# Arduino_extension_connectors.net
KiCad netlist of a schematic drawn in Altium Designer
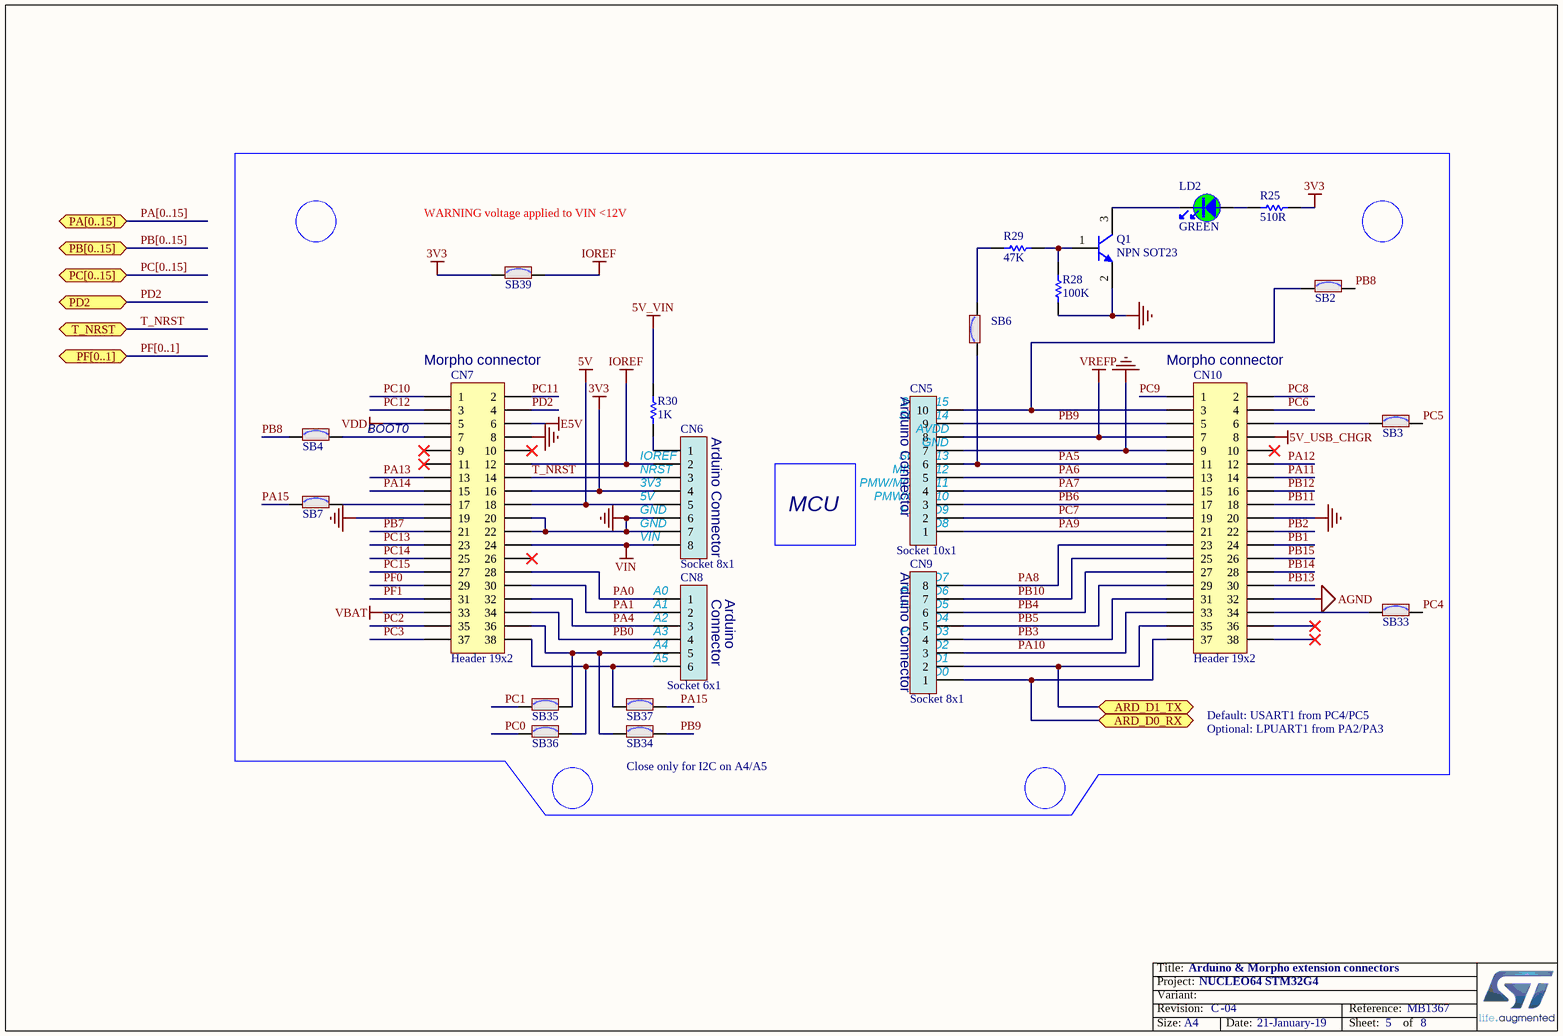
[diagram p0: Arduino_extension_connectors.SchDoc]

(export (version "E")
  (design (tool "Eeschema 10.0.6"))
  (components
    (comp (ref "CN5")
      (value "Socket 10x1")
      (footprint "CON_SAMTEC_SSW-110-03-X-S")
      (description "Socket, 10x1, 2.54mm, VR, TH, Height 8.51mm/10mm")
      (fields
        (field (name "INTERNAL_PART_NUMBER") "MCD-00262")
        (field (name "MANUFACTURER_PART_NUMBER") "SSW-110-03-x-S")
        (field (name "PROVIDED_BY") "SUBCO")
      )
      (libsource (lib "MCD_PARTS_database") (part "Socket 10x1"))
    )
    (comp (ref "CN6")
      (value "Socket 8x1")
      (footprint "CON_SAMTEC_SSW-108-03-X-S")
      (description "Socket, 8x1, 2.54mm, VR, TH, Height 8.51mm/10mm")
      (fields
        (field (name "INTERNAL_PART_NUMBER") "MCD-00261")
        (field (name "MANUFACTURER_PART_NUMBER") "SSW-108-03-x-S")
        (field (name "PROVIDED_BY") "SUBCO")
      )
      (libsource (lib "MCD_PARTS_database") (part "Socket 8x1"))
    )
    (comp (ref "CN7")
      (value "Header 19x2")
      (footprint "CON_SAMTEC_TSW-119-09-X-D")
      (description "Header, 19x2, 2,54mm, VR, TH, Height 5.84mm/10.16mm")
      (fields
        (field (name "INTERNAL_PART_NUMBER") "MCD-00213")
        (field (name "MANUFACTURER_PART_NUMBER") "TSW-119-09-x-D")
        (field (name "PROVIDED_BY") "SUBCO")
      )
      (libsource (lib "MCD_PARTS_database") (part "Header 19x2"))
    )
    (comp (ref "CN8")
      (value "Socket 6x1")
      (footprint "CON_SAMTEC_SSW-106-03-X-S")
      (description "Socket, 6x1, 2.54mm, VR, TH, Height 8.51mm/10mm")
      (fields
        (field (name "INTERNAL_PART_NUMBER") "MCD-00260")
        (field (name "MANUFACTURER_PART_NUMBER") "SSW-106-03-x-S")
        (field (name "PROVIDED_BY") "SUBCO")
      )
      (libsource (lib "MCD_PARTS_database") (part "Socket 6x1"))
    )
    (comp (ref "CN9")
      (value "Socket 8x1")
      (footprint "CON_SAMTEC_SSW-108-03-X-S")
      (description "Socket, 8x1, 2.54mm, VR, TH, Height 8.51mm/10mm")
      (fields
        (field (name "INTERNAL_PART_NUMBER") "MCD-00261")
        (field (name "MANUFACTURER_PART_NUMBER") "SSW-108-03-x-S")
        (field (name "PROVIDED_BY") "SUBCO")
      )
      (libsource (lib "") (part "Socket 8x1_1"))
    )
    (comp (ref "CN10")
      (value "Header 19x2")
      (footprint "CON_SAMTEC_TSW-119-09-X-D")
      (description "Header, 19x2, 2,54mm, VR, TH, Height 5.84mm/10.16mm")
      (fields
        (field (name "INTERNAL_PART_NUMBER") "MCD-00213")
        (field (name "MANUFACTURER_PART_NUMBER") "TSW-119-09-x-D")
        (field (name "PROVIDED_BY") "SUBCO")
      )
      (libsource (lib "MCD_PARTS_database") (part "Header 19x2"))
    )
    (comp (ref "LD2")
      (value "GREEN")
      (footprint "LED_0603_GREEN")
      (description "LED, Green, 0603")
      (fields
        (field (name "INTERNAL_PART_NUMBER") "MCD-00050")
        (field (name "MANUFACTURER_PART_NUMBER") "19-213SYGC/S530-E2/TR8")
        (field (name "PROVIDED_BY") "SUBCO")
      )
      (libsource (lib "MCD_PARTS_database") (part "LED_green"))
    )
    (comp (ref "Q1")
      (value "NPN SOT23")
      (footprint "NPN_SOT23")
      (description "NPN Bipolar Transistor")
      (fields
        (field (name "INTERNAL_PART_NUMBER") "MCD-00073")
        (field (name "MANUFACTURER_PART_NUMBER") "BSR14")
        (field (name "PROVIDED_BY") "SUBCO")
      )
      (libsource (lib "MCD_PARTS_database") (part "9013-SOT23"))
    )
    (comp (ref "R25")
      (value "510R")
      (footprint "R0603")
      (description "Resistor,510R,0603,1%,1/10W")
      (fields
        (field (name "INTERNAL_PART_NUMBER") "MCD-00225")
        (field (name "MANUFACTURER_PART_NUMBER") "RC0603FR-07510RL")
        (field (name "PROVIDED_BY") "SUBCO")
      )
      (libsource (lib "MCD_PARTS_database") (part "Resistor"))
    )
    (comp (ref "R28")
      (value "100K")
      (footprint "R0603")
      (description "Resistor,100K,0603,1%,1/10W")
      (fields
        (field (name "INTERNAL_PART_NUMBER") "MCD-00223")
        (field (name "MANUFACTURER_PART_NUMBER") "RC0603FR-07100KL")
        (field (name "PROVIDED_BY") "Subcon")
      )
      (libsource (lib "MCD_PARTS_database") (part "Resistor"))
    )
    (comp (ref "R29")
      (value "47K")
      (footprint "R0603")
      (description "Resistor,47K,0603,1%,1/10W")
      (fields
        (field (name "INTERNAL_PART_NUMBER") "MCD-00222")
        (field (name "MANUFACTURER_PART_NUMBER") "RC0603FR-0747KL")
        (field (name "PROVIDED_BY") "SUBCO")
      )
      (libsource (lib "MCD_PARTS_database") (part "Resistor"))
    )
    (comp (ref "R30")
      (value "1K")
      (footprint "R0603")
      (description "Resistor,1K,0603,1%,1/10W")
      (fields
        (field (name "INTERNAL_PART_NUMBER") "MCD-00070")
        (field (name "MANUFACTURER_PART_NUMBER") "RC0603FR-071KL")
        (field (name "PROVIDED_BY") "Subcon")
      )
      (libsource (lib "MCD_PARTS_database") (part "Resistor"))
    )
    (comp (ref "SB2")
      (value "~")
      (footprint "SOLDER-BRIDGE_R0603-0R")
      (description "Solder Bridge ON")
      (fields
        (field (name "INTERNAL_PART_NUMBER") "MCD-00071")
        (field (name "MANUFACTURER_PART_NUMBER") "RC0603JR-070RL")
        (field (name "PROVIDED_BY") "SUBCO")
      )
      (libsource (lib "MCD_PARTS_database") (part "SB_ON"))
    )
    (comp (ref "SB3")
      (value "~")
      (footprint "SOLDER-BRIDGE_R0603-0R")
      (description "Solder Bridge ON")
      (fields
        (field (name "INTERNAL_PART_NUMBER") "MCD-00071")
        (field (name "MANUFACTURER_PART_NUMBER") "RC0603JR-070RL")
        (field (name "PROVIDED_BY") "SUBCO")
      )
      (libsource (lib "MCD_PARTS_database") (part "SB_ON"))
    )
    (comp (ref "SB4")
      (value "~")
      (footprint "SOLDER-BRIDGE_R0603-0R")
      (description "Solder Bridge ON")
      (fields
        (field (name "INTERNAL_PART_NUMBER") "MCD-00071")
        (field (name "MANUFACTURER_PART_NUMBER") "RC0603JR-070RL")
        (field (name "PROVIDED_BY") "SUBCO")
      )
      (libsource (lib "MCD_PARTS_database") (part "SB_ON"))
    )
    (comp (ref "SB6")
      (value "~")
      (footprint "SOLDER-BRIDGE_R0603-0R")
      (description "Solder Bridge ON")
      (fields
        (field (name "INTERNAL_PART_NUMBER") "MCD-00071")
        (field (name "MANUFACTURER_PART_NUMBER") "RC0603JR-070RL")
        (field (name "PROVIDED_BY") "SUBCO")
      )
      (libsource (lib "") (part "SB_ON_1"))
    )
    (comp (ref "SB7")
      (value "~")
      (footprint "SOLDER-BRIDGE_R0603-0R")
      (description "Solder Bridge ON")
      (fields
        (field (name "INTERNAL_PART_NUMBER") "MCD-00071")
        (field (name "MANUFACTURER_PART_NUMBER") "RC0603JR-070RL")
        (field (name "PROVIDED_BY") "SUBCO")
      )
      (libsource (lib "MCD_PARTS_database") (part "SB_ON"))
    )
    (comp (ref "SB33")
      (value "~")
      (footprint "SOLDER-BRIDGE_R0603-0R")
      (description "Solder Bridge ON")
      (fields
        (field (name "INTERNAL_PART_NUMBER") "MCD-00071")
        (field (name "MANUFACTURER_PART_NUMBER") "RC0603JR-070RL")
        (field (name "PROVIDED_BY") "SUBCO")
      )
      (libsource (lib "MCD_PARTS_database") (part "SB_ON"))
    )
    (comp (ref "SB34")
      (value "~")
      (footprint "SOLDER-BRIDGE_R0603-0R")
      (description "Solder Bridge ON")
      (fields
        (field (name "INTERNAL_PART_NUMBER") "MCD-00071")
        (field (name "MANUFACTURER_PART_NUMBER") "RC0603JR-070RL")
        (field (name "PROVIDED_BY") "SUBCO")
      )
      (libsource (lib "MCD_PARTS_database") (part "SB_ON"))
    )
    (comp (ref "SB35")
      (value "~")
      (footprint "SOLDER-BRIDGE_R0603-0R")
      (description "Solder Bridge ON")
      (fields
        (field (name "INTERNAL_PART_NUMBER") "MCD-00071")
        (field (name "MANUFACTURER_PART_NUMBER") "RC0603JR-070RL")
        (field (name "PROVIDED_BY") "SUBCO")
      )
      (libsource (lib "MCD_PARTS_database") (part "SB_ON"))
    )
    (comp (ref "SB36")
      (value "~")
      (footprint "SOLDER-BRIDGE_R0603-0R")
      (description "Solder Bridge ON")
      (fields
        (field (name "INTERNAL_PART_NUMBER") "MCD-00071")
        (field (name "MANUFACTURER_PART_NUMBER") "RC0603JR-070RL")
        (field (name "PROVIDED_BY") "SUBCO")
      )
      (libsource (lib "MCD_PARTS_database") (part "SB_ON"))
    )
    (comp (ref "SB37")
      (value "~")
      (footprint "SOLDER-BRIDGE_R0603-0R")
      (description "Solder Bridge ON")
      (fields
        (field (name "INTERNAL_PART_NUMBER") "MCD-00071")
        (field (name "MANUFACTURER_PART_NUMBER") "RC0603JR-070RL")
        (field (name "PROVIDED_BY") "SUBCO")
      )
      (libsource (lib "MCD_PARTS_database") (part "SB_ON"))
    )
    (comp (ref "SB39")
      (value "~")
      (footprint "SOLDER-BRIDGE_R0603-0R")
      (description "Solder Bridge ON")
      (fields
        (field (name "INTERNAL_PART_NUMBER") "MCD-00071")
        (field (name "MANUFACTURER_PART_NUMBER") "RC0603JR-070RL")
        (field (name "PROVIDED_BY") "SUBCO")
      )
      (libsource (lib "MCD_PARTS_database") (part "SB_ON"))
    )
  )
  (nets
    (net (code "3") (name "/ARD_D0_RX") (class "Default")
      (node (ref "CN10") (pin "37") (pinfunction "37_37") (pintype "passive"))
      (node (ref "CN9") (pin "1") (pinfunction "1_1") (pintype "passive"))
    )
    (net (code "4") (name "/ARD_D1_TX") (class "Default")
      (node (ref "CN10") (pin "35") (pinfunction "35_35") (pintype "passive"))
      (node (ref "CN9") (pin "2") (pinfunction "2_2") (pintype "passive"))
    )
    (net (code "5") (name "/PA0") (class "Default")
      (node (ref "CN7") (pin "28") (pinfunction "28_28") (pintype "passive"))
      (node (ref "CN8") (pin "1") (pinfunction "1_1") (pintype "passive"))
    )
    (net (code "6") (name "/PA1") (class "Default")
      (node (ref "CN7") (pin "30") (pinfunction "30_30") (pintype "passive"))
      (node (ref "CN8") (pin "2") (pinfunction "2_2") (pintype "passive"))
    )
    (net (code "7") (name "/PA4") (class "Default")
      (node (ref "CN7") (pin "32") (pinfunction "32_32") (pintype "passive"))
      (node (ref "CN8") (pin "3") (pinfunction "3_3") (pintype "passive"))
    )
    (net (code "8") (name "/PA5") (class "Default")
      (node (ref "CN10") (pin "11") (pinfunction "11_11") (pintype "passive"))
      (node (ref "CN5") (pin "6") (pinfunction "6_6") (pintype "passive"))
      (node (ref "SB6") (pin "1") (pinfunction "1_1") (pintype "passive"))
    )
    (net (code "9") (name "/PA6") (class "Default")
      (node (ref "CN10") (pin "13") (pinfunction "13_13") (pintype "passive"))
      (node (ref "CN5") (pin "5") (pinfunction "5_5") (pintype "passive"))
    )
    (net (code "10") (name "/PA7") (class "Default")
      (node (ref "CN10") (pin "15") (pinfunction "15_15") (pintype "passive"))
      (node (ref "CN5") (pin "4") (pinfunction "4_4") (pintype "passive"))
    )
    (net (code "11") (name "/PA8") (class "Default")
      (node (ref "CN10") (pin "23") (pinfunction "23_23") (pintype "passive"))
      (node (ref "CN9") (pin "8") (pinfunction "8_8") (pintype "passive"))
    )
    (net (code "12") (name "/PA9") (class "Default")
      (node (ref "CN10") (pin "21") (pinfunction "21_21") (pintype "passive"))
      (node (ref "CN5") (pin "1") (pinfunction "1_1") (pintype "passive"))
    )
    (net (code "13") (name "/PA10") (class "Default")
      (node (ref "CN10") (pin "33") (pinfunction "33_33") (pintype "passive"))
      (node (ref "CN9") (pin "3") (pinfunction "3_3") (pintype "passive"))
    )
    (net (code "14") (name "/PA11") (class "Default")
      (node (ref "CN10") (pin "14") (pinfunction "14_14") (pintype "passive"))
    )
    (net (code "15") (name "/PA12") (class "Default")
      (node (ref "CN10") (pin "12") (pinfunction "12_12") (pintype "passive"))
    )
    (net (code "16") (name "/PA13") (class "Default")
      (node (ref "CN7") (pin "13") (pinfunction "13_13") (pintype "passive"))
    )
    (net (code "17") (name "/PA14") (class "Default")
      (node (ref "CN7") (pin "15") (pinfunction "15_15") (pintype "passive"))
    )
    (net (code "18") (name "/PA15") (class "Default")
      (node (ref "SB37") (pin "2") (pinfunction "2_2") (pintype "passive"))
      (node (ref "SB7") (pin "1") (pinfunction "1_1") (pintype "passive"))
    )
    (net (code "20") (name "/PB0") (class "Default")
      (node (ref "CN7") (pin "34") (pinfunction "34_34") (pintype "passive"))
      (node (ref "CN8") (pin "4") (pinfunction "4_4") (pintype "passive"))
    )
    (net (code "21") (name "/PB1") (class "Default")
      (node (ref "CN10") (pin "24") (pinfunction "24_24") (pintype "passive"))
    )
    (net (code "22") (name "/PB2") (class "Default")
      (node (ref "CN10") (pin "22") (pinfunction "22_22") (pintype "passive"))
    )
    (net (code "23") (name "/PB3") (class "Default")
      (node (ref "CN10") (pin "31") (pinfunction "31_31") (pintype "passive"))
      (node (ref "CN9") (pin "4") (pinfunction "4_4") (pintype "passive"))
    )
    (net (code "24") (name "/PB4") (class "Default")
      (node (ref "CN10") (pin "27") (pinfunction "27_27") (pintype "passive"))
      (node (ref "CN9") (pin "6") (pinfunction "6_6") (pintype "passive"))
    )
    (net (code "25") (name "/PB5") (class "Default")
      (node (ref "CN10") (pin "29") (pinfunction "29_29") (pintype "passive"))
      (node (ref "CN9") (pin "5") (pinfunction "5_5") (pintype "passive"))
    )
    (net (code "26") (name "/PB6") (class "Default")
      (node (ref "CN10") (pin "17") (pinfunction "17_17") (pintype "passive"))
      (node (ref "CN5") (pin "3") (pinfunction "3_3") (pintype "passive"))
    )
    (net (code "27") (name "/PB7") (class "Default")
      (node (ref "CN7") (pin "21") (pinfunction "21_21") (pintype "passive"))
    )
    (net (code "28") (name "/PB8") (class "Default")
      (node (ref "SB2") (pin "2") (pinfunction "2_2") (pintype "passive"))
      (node (ref "SB4") (pin "1") (pinfunction "1_1") (pintype "passive"))
    )
    (net (code "29") (name "/PB9") (class "Default")
      (node (ref "CN10") (pin "5") (pinfunction "5_5") (pintype "passive"))
      (node (ref "CN5") (pin "9") (pinfunction "9_9") (pintype "passive"))
      (node (ref "SB34") (pin "2") (pinfunction "2_2") (pintype "passive"))
    )
    (net (code "30") (name "/PB10") (class "Default")
      (node (ref "CN10") (pin "25") (pinfunction "25_25") (pintype "passive"))
      (node (ref "CN9") (pin "7") (pinfunction "7_7") (pintype "passive"))
    )
    (net (code "31") (name "/PB11") (class "Default")
      (node (ref "CN10") (pin "18") (pinfunction "18_18") (pintype "passive"))
    )
    (net (code "32") (name "/PB12") (class "Default")
      (node (ref "CN10") (pin "16") (pinfunction "16_16") (pintype "passive"))
    )
    (net (code "33") (name "/PB13") (class "Default")
      (node (ref "CN10") (pin "30") (pinfunction "30_30") (pintype "passive"))
    )
    (net (code "34") (name "/PB14") (class "Default")
      (node (ref "CN10") (pin "28") (pinfunction "28_28") (pintype "passive"))
    )
    (net (code "35") (name "/PB15") (class "Default")
      (node (ref "CN10") (pin "26") (pinfunction "26_26") (pintype "passive"))
    )
    (net (code "37") (name "/PC0") (class "Default")
      (node (ref "SB36") (pin "1") (pinfunction "1_1") (pintype "passive"))
    )
    (net (code "38") (name "/PC1") (class "Default")
      (node (ref "SB35") (pin "1") (pinfunction "1_1") (pintype "passive"))
    )
    (net (code "39") (name "/PC2") (class "Default")
      (node (ref "CN7") (pin "35") (pinfunction "35_35") (pintype "passive"))
    )
    (net (code "40") (name "/PC3") (class "Default")
      (node (ref "CN7") (pin "37") (pinfunction "37_37") (pintype "passive"))
    )
    (net (code "41") (name "/PC4") (class "Default")
      (node (ref "SB33") (pin "2") (pinfunction "2_2") (pintype "passive"))
    )
    (net (code "42") (name "/PC5") (class "Default")
      (node (ref "SB3") (pin "2") (pinfunction "2_2") (pintype "passive"))
    )
    (net (code "43") (name "/PC6") (class "Default")
      (node (ref "CN10") (pin "4") (pinfunction "4_4") (pintype "passive"))
    )
    (net (code "44") (name "/PC7") (class "Default")
      (node (ref "CN10") (pin "19") (pinfunction "19_19") (pintype "passive"))
      (node (ref "CN5") (pin "2") (pinfunction "2_2") (pintype "passive"))
    )
    (net (code "45") (name "/PC8") (class "Default")
      (node (ref "CN10") (pin "2") (pinfunction "2_2") (pintype "passive"))
    )
    (net (code "46") (name "/PC9") (class "Default")
      (node (ref "CN10") (pin "1") (pinfunction "1_1") (pintype "passive"))
    )
    (net (code "47") (name "/PC10") (class "Default")
      (node (ref "CN7") (pin "1") (pinfunction "1_1") (pintype "passive"))
    )
    (net (code "48") (name "/PC11") (class "Default")
      (node (ref "CN7") (pin "2") (pinfunction "2_2") (pintype "passive"))
    )
    (net (code "49") (name "/PC12") (class "Default")
      (node (ref "CN7") (pin "3") (pinfunction "3_3") (pintype "passive"))
    )
    (net (code "50") (name "/PC13") (class "Default")
      (node (ref "CN7") (pin "23") (pinfunction "23_23") (pintype "passive"))
    )
    (net (code "51") (name "/PC14") (class "Default")
      (node (ref "CN7") (pin "25") (pinfunction "25_25") (pintype "passive"))
    )
    (net (code "52") (name "/PC15") (class "Default")
      (node (ref "CN7") (pin "27") (pinfunction "27_27") (pintype "passive"))
    )
    (net (code "54") (name "/PD2") (class "Default")
      (node (ref "CN7") (pin "4") (pinfunction "4_4") (pintype "passive"))
    )
    (net (code "55") (name "/PF0") (class "Default")
      (node (ref "CN7") (pin "29") (pinfunction "29_29") (pintype "passive"))
    )
    (net (code "56") (name "/PF1") (class "Default")
      (node (ref "CN7") (pin "31") (pinfunction "31_31") (pintype "passive"))
    )
    (net (code "58") (name "/T_NRST") (class "Default")
      (node (ref "CN6") (pin "3") (pinfunction "3_3") (pintype "passive"))
      (node (ref "CN7") (pin "14") (pinfunction "14_14") (pintype "passive"))
    )
    (net (code "59") (name "3V3") (class "Default")
      (node (ref "CN6") (pin "4") (pinfunction "4_4") (pintype "passive"))
      (node (ref "CN7") (pin "16") (pinfunction "16_16") (pintype "passive"))
      (node (ref "R25") (pin "1") (pinfunction "1_1") (pintype "passive"))
      (node (ref "SB39") (pin "1") (pinfunction "1_1") (pintype "passive"))
    )
    (net (code "60") (name "5V") (class "Default")
      (node (ref "CN6") (pin "5") (pinfunction "5_5") (pintype "passive"))
      (node (ref "CN7") (pin "18") (pinfunction "18_18") (pintype "passive"))
    )
    (net (code "61") (name "5V_USB_CHGR") (class "Default")
      (node (ref "CN10") (pin "8") (pinfunction "8_8") (pintype "passive"))
    )
    (net (code "62") (name "5V_VIN") (class "Default")
      (node (ref "R30") (pin "2") (pinfunction "2_2") (pintype "passive"))
    )
    (net (code "63") (name "AGND") (class "Default")
      (node (ref "CN10") (pin "32") (pinfunction "32_32") (pintype "passive"))
    )
    (net (code "64") (name "E5V") (class "Default")
      (node (ref "CN7") (pin "6") (pinfunction "6_6") (pintype "passive"))
    )
    (net (code "65") (name "GND") (class "Default")
      (node (ref "CN10") (pin "20") (pinfunction "20_20") (pintype "passive"))
      (node (ref "CN10") (pin "9") (pinfunction "9_9") (pintype "passive"))
      (node (ref "CN5") (pin "7") (pinfunction "7_7") (pintype "passive"))
      (node (ref "CN6") (pin "6") (pinfunction "6_6") (pintype "passive"))
      (node (ref "CN6") (pin "7") (pinfunction "7_7") (pintype "passive"))
      (node (ref "CN7") (pin "19") (pinfunction "19_19") (pintype "passive"))
      (node (ref "CN7") (pin "20") (pinfunction "20_20") (pintype "passive"))
      (node (ref "CN7") (pin "22") (pinfunction "22_22") (pintype "passive"))
      (node (ref "CN7") (pin "8") (pinfunction "8_8") (pintype "passive"))
      (node (ref "Q1") (pin "2") (pinfunction "E_2") (pintype "passive"))
      (node (ref "R28") (pin "1") (pinfunction "1_1") (pintype "passive"))
    )
    (net (code "66") (name "IOREF") (class "Default")
      (node (ref "CN6") (pin "2") (pinfunction "2_2") (pintype "passive"))
      (node (ref "CN7") (pin "12") (pinfunction "12_12") (pintype "passive"))
      (node (ref "SB39") (pin "2") (pinfunction "2_2") (pintype "passive"))
    )
    (net (code "67") (name "Net-(CN6-Pad1)") (class "Default")
      (node (ref "CN6") (pin "1") (pinfunction "1_1") (pintype "passive"))
      (node (ref "R30") (pin "1") (pinfunction "1_1") (pintype "passive"))
    )
    (net (code "68") (name "Net-(CN7-Pad7)") (class "Default")
      (node (ref "CN7") (pin "7") (pinfunction "7_7") (pintype "passive"))
      (node (ref "SB4") (pin "2") (pinfunction "2_2") (pintype "passive"))
    )
    (net (code "69") (name "Net-(CN7-Pad17)") (class "Default")
      (node (ref "CN7") (pin "17") (pinfunction "17_17") (pintype "passive"))
      (node (ref "SB7") (pin "2") (pinfunction "2_2") (pintype "passive"))
    )
    (net (code "70") (name "Net-(CN7-Pad36)") (class "Default")
      (node (ref "CN7") (pin "36") (pinfunction "36_36") (pintype "passive"))
      (node (ref "CN8") (pin "5") (pinfunction "5_5") (pintype "passive"))
      (node (ref "SB34") (pin "1") (pinfunction "1_1") (pintype "passive"))
      (node (ref "SB35") (pin "2") (pinfunction "2_2") (pintype "passive"))
    )
    (net (code "71") (name "Net-(CN7-Pad38)") (class "Default")
      (node (ref "CN7") (pin "38") (pinfunction "38_38") (pintype "passive"))
      (node (ref "CN8") (pin "6") (pinfunction "6_6") (pintype "passive"))
      (node (ref "SB36") (pin "2") (pinfunction "2_2") (pintype "passive"))
      (node (ref "SB37") (pin "1") (pinfunction "1_1") (pintype "passive"))
    )
    (net (code "72") (name "Net-(CN10-Pad3)") (class "Default")
      (node (ref "CN10") (pin "3") (pinfunction "3_3") (pintype "passive"))
      (node (ref "CN5") (pin "10") (pinfunction "10_10") (pintype "passive"))
      (node (ref "SB2") (pin "1") (pinfunction "1_1") (pintype "passive"))
    )
    (net (code "73") (name "Net-(CN10-Pad6)") (class "Default")
      (node (ref "CN10") (pin "6") (pinfunction "6_6") (pintype "passive"))
      (node (ref "SB3") (pin "1") (pinfunction "1_1") (pintype "passive"))
    )
    (net (code "74") (name "Net-(CN10-Pad34)") (class "Default")
      (node (ref "CN10") (pin "34") (pinfunction "34_34") (pintype "passive"))
      (node (ref "SB33") (pin "1") (pinfunction "1_1") (pintype "passive"))
    )
    (net (code "75") (name "Net-(LD2-Pad1)") (class "Default")
      (node (ref "LD2") (pin "1") (pintype "passive"))
      (node (ref "R25") (pin "2") (pinfunction "2_2") (pintype "passive"))
    )
    (net (code "76") (name "Net-(Q1-B)") (class "Default")
      (node (ref "Q1") (pin "1") (pinfunction "B_1") (pintype "passive"))
      (node (ref "R28") (pin "2") (pinfunction "2_2") (pintype "passive"))
      (node (ref "R29") (pin "2") (pinfunction "2_2") (pintype "passive"))
    )
    (net (code "77") (name "Net-(Q1-C)") (class "Default")
      (node (ref "LD2") (pin "2") (pintype "passive"))
      (node (ref "Q1") (pin "3") (pinfunction "C_3") (pintype "passive"))
    )
    (net (code "78") (name "Net-(R29-Pad1)") (class "Default")
      (node (ref "R29") (pin "1") (pinfunction "1_1") (pintype "passive"))
      (node (ref "SB6") (pin "2") (pinfunction "2_2") (pintype "passive"))
    )
    (net (code "79") (name "VBAT") (class "Default")
      (node (ref "CN7") (pin "33") (pinfunction "33_33") (pintype "passive"))
    )
    (net (code "80") (name "VDD") (class "Default")
      (node (ref "CN7") (pin "5") (pinfunction "5_5") (pintype "passive"))
    )
    (net (code "81") (name "VIN") (class "Default")
      (node (ref "CN6") (pin "8") (pinfunction "8_8") (pintype "passive"))
      (node (ref "CN7") (pin "24") (pinfunction "24_24") (pintype "passive"))
    )
    (net (code "82") (name "VREFP") (class "Default")
      (node (ref "CN10") (pin "7") (pinfunction "7_7") (pintype "passive"))
      (node (ref "CN5") (pin "8") (pinfunction "8_8") (pintype "passive"))
    )
    (net (code "83") (name "unconnected-(CN7-Pad9)") (class "Default")
      (node (ref "CN7") (pin "9") (pinfunction "9_9") (pintype "passive+no_connect"))
    )
    (net (code "84") (name "unconnected-(CN7-Pad10)") (class "Default")
      (node (ref "CN7") (pin "10") (pinfunction "10_10") (pintype "passive+no_connect"))
    )
    (net (code "85") (name "unconnected-(CN7-Pad11)") (class "Default")
      (node (ref "CN7") (pin "11") (pinfunction "11_11") (pintype "passive+no_connect"))
    )
    (net (code "86") (name "unconnected-(CN7-Pad26)") (class "Default")
      (node (ref "CN7") (pin "26") (pinfunction "26_26") (pintype "passive+no_connect"))
    )
    (net (code "87") (name "unconnected-(CN10-Pad10)") (class "Default")
      (node (ref "CN10") (pin "10") (pinfunction "10_10") (pintype "passive+no_connect"))
    )
    (net (code "88") (name "unconnected-(CN10-Pad36)") (class "Default")
      (node (ref "CN10") (pin "36") (pinfunction "36_36") (pintype "passive+no_connect"))
    )
    (net (code "89") (name "unconnected-(CN10-Pad38)") (class "Default")
      (node (ref "CN10") (pin "38") (pinfunction "38_38") (pintype "passive+no_connect"))
    )
  )
)
